# OC_PROT.net
KiCad netlist of a schematic drawn in Altium Designer
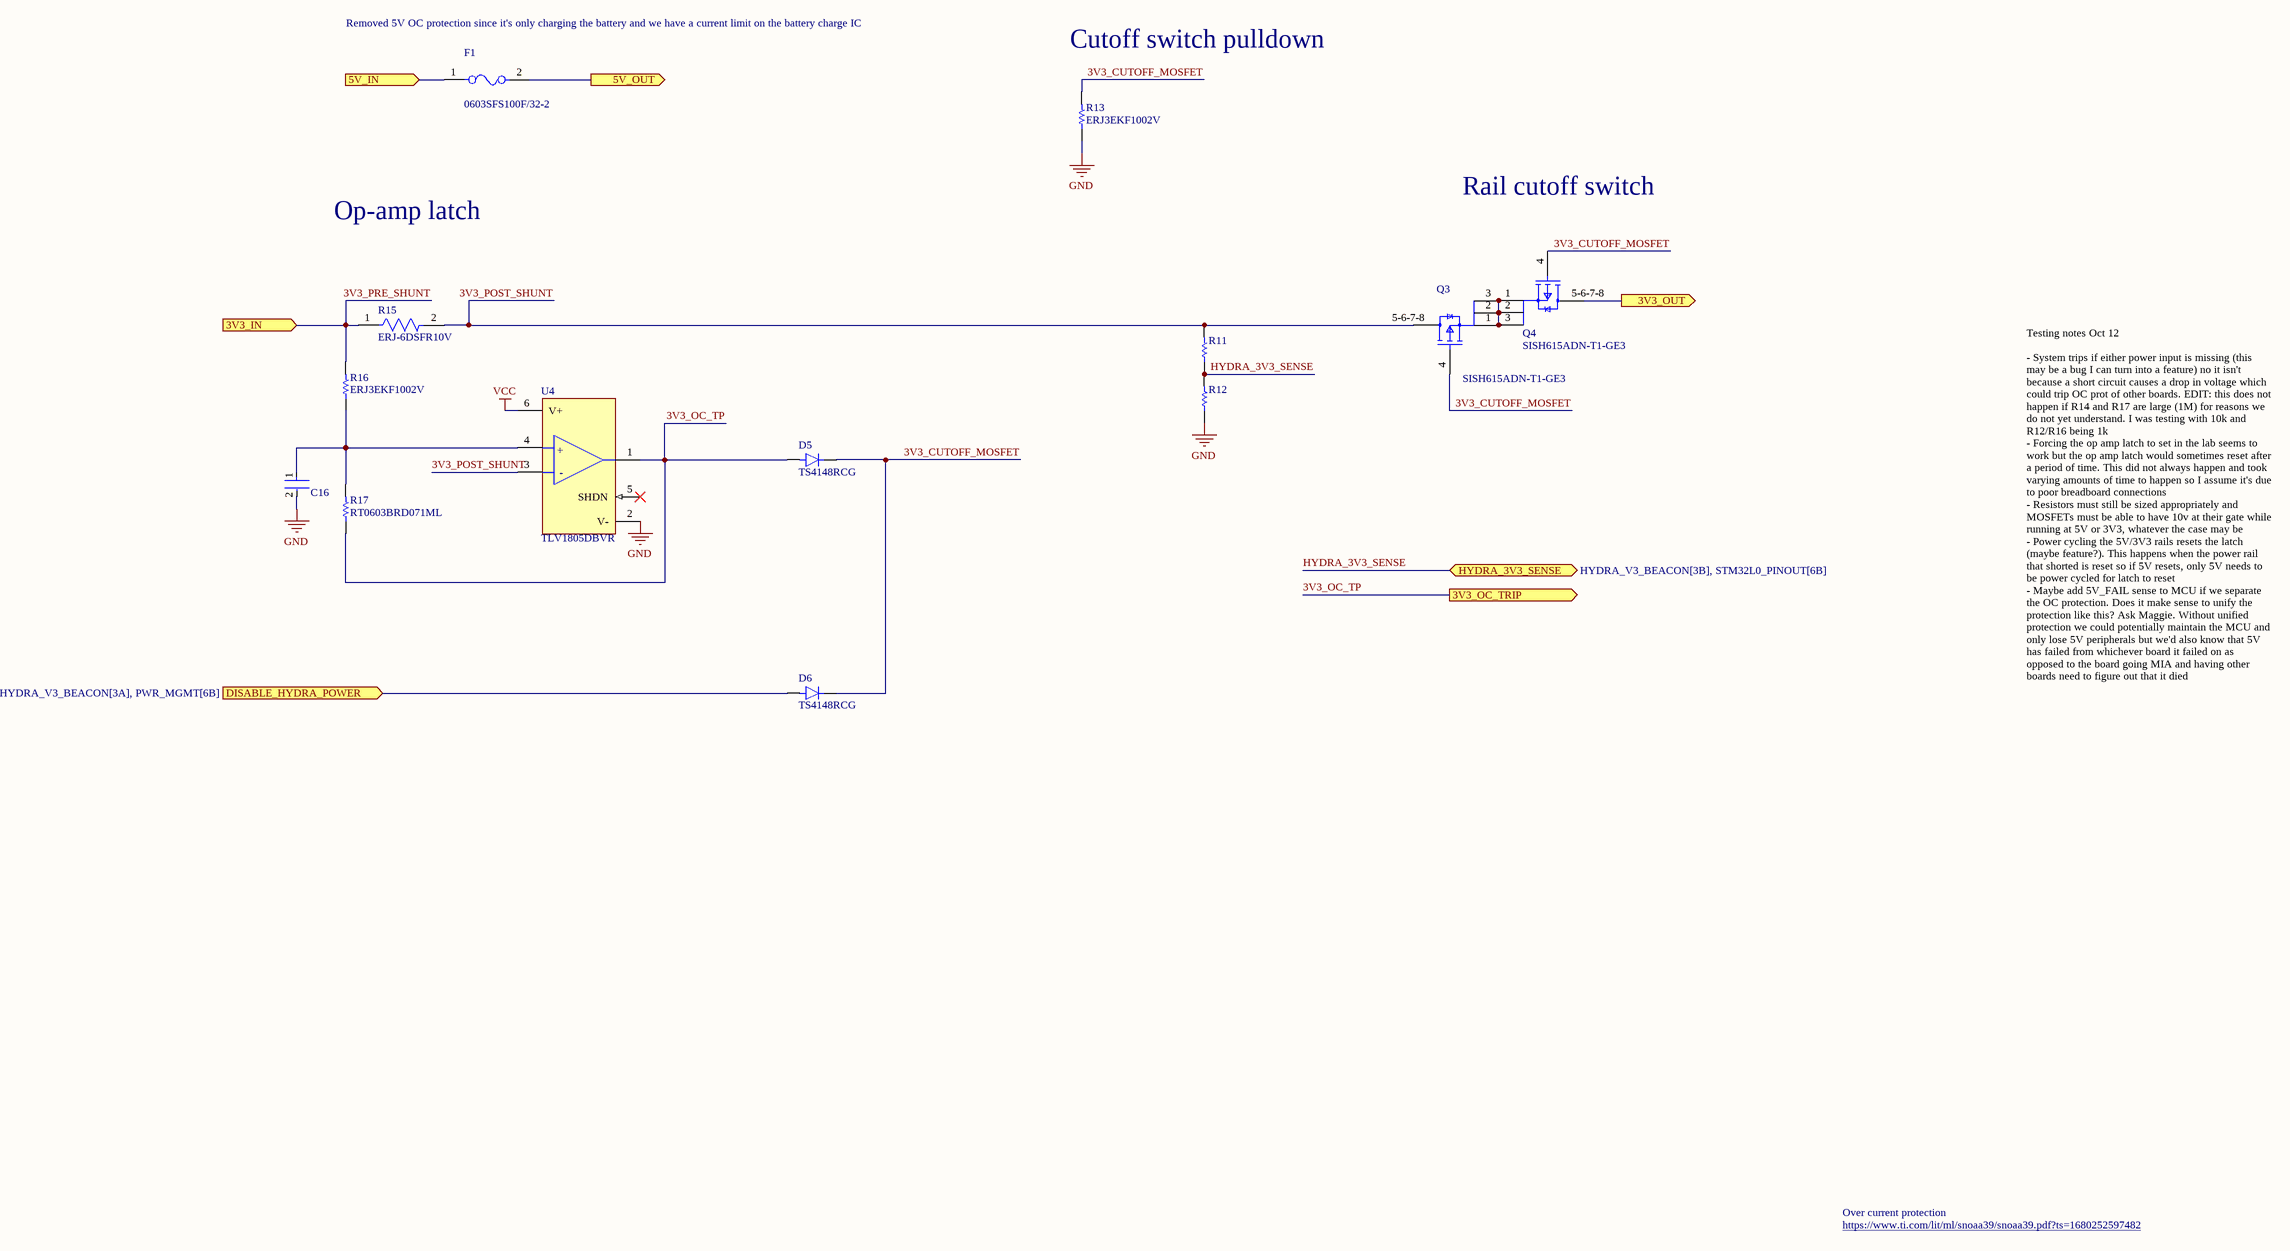
[diagram p0: OC_PROT.SchDoc]

(export (version "E")
  (design (tool "Eeschema 10.0.6"))
  (components
    (comp (ref "C16")
      (value "C0402C104K8PACTU")
      (footprint "FP-C0402-BB-MFG")
      (description "CAP CER 0.1UF 10V X5R 0402")
      (fields (field (name "MANUFACTURER") "Kemet") (field (name "TOLERANCE") "0.1"))
      (libsource (lib "Altium Content Vault") (part "b4654b650e69147ec39a6b967a45e02"))
    )
    (comp (ref "D5")
      (value "TS4148RCG")
      (footprint "TS4148RCG-Footprint-1")
      (description "SMD Si-Diode 75V 100mA 0603")
      (libsource (lib "uORocketry Hardware") (part "TS4148RCG"))
    )
    (comp (ref "D6")
      (value "TS4148RCG")
      (footprint "TS4148RCG-Footprint-1")
      (description "SMD Si-Diode 75V 100mA 0603")
      (libsource (lib "uORocketry Hardware") (part "TS4148RCG"))
    )
    (comp (ref "F1")
      (value "0603SFS100F/32-2")
      (footprint "FP-0603SFS-MFG")
      (description "FUSE BOARD MOUNT 1A 32VDC 0603")
      (fields
        (field (name "OCTOPART") "https://octopart.com/0603sfs100f%2F32-2-littelfuse-74214378")
        (field (name "MANUFACTURER") "Littelfuse")
      )
      (libsource (lib "Altium Content Vault") (part "5bcf9b9f640e542cf0359d10258e979"))
    )
    (comp (ref "Q3")
      (value "SISH615ADN-T1-GE3")
      (footprint "SISH615ADN-T1-GE3-Footprint-1")
      (description "Trans MOSFET P-CH 20V 22.1A 8-Pin PowerPAK 1212 EP T/R")
      (libsource (lib "uORocketry Hardware") (part "SISH615ADN-T1-GE3-Symbol-1"))
    )
    (comp (ref "Q4")
      (value "SISH615ADN-T1-GE3")
      (footprint "SISH615ADN-T1-GE3-Footprint-1")
      (description "Trans MOSFET P-CH 20V 22.1A 8-Pin PowerPAK 1212 EP T/R")
      (libsource (lib "uORocketry Hardware") (part "SISH615ADN-T1-GE3-Symbol-1"))
    )
    (comp (ref "R11")
      (value "ERJ3EKF1002V")
      (footprint "RESC1609X55X30LL15T15")
      (description "Chip Resistor, 10 KOhm, +/- 1%, 0.1 W, -55 to 155 degC, 0603 (1608 Metric), RoHS, Tape and Reel")
      (fields (field (name "TOLERANCE") "1%") (field (name "MANUFACTURER") "Panasonic"))
      (libsource (lib "Altium Content Vault") (part "RES-2"))
    )
    (comp (ref "R12")
      (value "ERJ3EKF1002V")
      (footprint "RESC1609X55X30LL15T15")
      (description "Chip Resistor, 10 KOhm, +/- 1%, 0.1 W, -55 to 155 degC, 0603 (1608 Metric), RoHS, Tape and Reel")
      (fields (field (name "TOLERANCE") "1%") (field (name "MANUFACTURER") "Panasonic"))
      (libsource (lib "Altium Content Vault") (part "RES-2"))
    )
    (comp (ref "R13")
      (value "ERJ3EKF1002V")
      (footprint "RESC1609X55X30LL15T15")
      (description "Chip Resistor, 10 KOhm, +/- 1%, 0.1 W, -55 to 155 degC, 0603 (1608 Metric), RoHS, Tape and Reel")
      (fields (field (name "TOLERANCE") "1%") (field (name "MANUFACTURER") "Panasonic"))
      (libsource (lib "Altium Content Vault") (part "RES-2"))
    )
    (comp (ref "R15")
      (value "ERJ-6DSFR10V")
      (footprint "FP-ERJ6D-MFG")
      (description "RES 0.1 OHM 1% 1/2W 0805")
      (fields (field (name "TOLERANCE") "1%"))
      (libsource (lib "Altium Content Vault") (part "1029c3af85768c4190bb7ad29bc67b5"))
    )
    (comp (ref "R16")
      (value "ERJ3EKF1002V")
      (footprint "RESC1609X55X30LL15T15")
      (description "Chip Resistor, 10 KOhm, +/- 1%, 0.1 W, -55 to 155 degC, 0603 (1608 Metric), RoHS, Tape and Reel")
      (fields (field (name "TOLERANCE") "1%") (field (name "MANUFACTURER") "Panasonic"))
      (libsource (lib "Altium Content Vault") (part "RES-2"))
    )
    (comp (ref "R17")
      (value "RT0603BRD071ML")
      (footprint "RESC1608X55X30NL20T20")
      (fields (field (name "MANUFACTURER") "Panasonic") (field (name "PART NUMBER") "ERA-3AEB163V"))
      (libsource (lib "Altium Content Vault") (part "RES"))
    )
    (comp (ref "U4")
      (value "TLV1805DBVR")
      (footprint "FP-DBV0006A-IPC_C")
      (description "40V, RAIL-TO-RAIL INPUT, PUSH-PU")
      (libsource (lib "Altium Content Vault") (part "c7aa3bc3dbf0dc8b0b0354779bd1228"))
    )
  )
  (nets
    (net (code "1") (name "/3V3_CUTOFF_MOSFET") (class "Default")
      (node (ref "D5") (pin "C") (pinfunction "K_C") (pintype "passive"))
      (node (ref "D6") (pin "C") (pinfunction "K_C") (pintype "passive"))
      (node (ref "Q3") (pin "4") (pinfunction "G_4") (pintype "passive"))
      (node (ref "Q4") (pin "4") (pinfunction "G_4") (pintype "passive"))
      (node (ref "R13") (pin "2") (pinfunction "2_2") (pintype "passive"))
    )
    (net (code "2") (name "/3V3_OC_TP") (class "Default")
      (node (ref "D5") (pin "A") (pinfunction "A_A") (pintype "passive"))
      (node (ref "R17") (pin "1") (pinfunction "1_1") (pintype "passive"))
      (node (ref "U4") (pin "1") (pinfunction "OUT_1") (pintype "passive"))
    )
    (net (code "3") (name "/3V3_OUT") (class "Default")
      (node (ref "Q4") (pin "5-6-7-8") (pinfunction "D_5-6-7-8") (pintype "passive"))
    )
    (net (code "4") (name "/3V3_POST_SHUNT") (class "Default")
      (node (ref "Q3") (pin "5-6-7-8") (pinfunction "D_5-6-7-8") (pintype "passive"))
      (node (ref "R11") (pin "2") (pinfunction "2_2") (pintype "passive"))
      (node (ref "R15") (pin "2") (pinfunction "2_2") (pintype "passive"))
      (node (ref "U4") (pin "3") (pinfunction "-IN_3") (pintype "tri_state"))
    )
    (net (code "5") (name "/3V3_PRE_SHUNT") (class "Default")
      (node (ref "R15") (pin "1") (pinfunction "1_1") (pintype "passive"))
      (node (ref "R16") (pin "2") (pinfunction "2_2") (pintype "passive"))
    )
    (net (code "6") (name "/5V_IN") (class "Default")
      (node (ref "F1") (pin "1") (pinfunction "1_1") (pintype "passive"))
    )
    (net (code "7") (name "/5V_OUT") (class "Default")
      (node (ref "F1") (pin "2") (pinfunction "2_2") (pintype "passive"))
    )
    (net (code "8") (name "/DISABLE_HYDRA_POWER") (class "Default")
      (node (ref "D6") (pin "A") (pinfunction "A_A") (pintype "passive"))
    )
    (net (code "9") (name "/HYDRA_3V3_SENSE") (class "Default")
      (node (ref "R11") (pin "1") (pinfunction "1_1") (pintype "passive"))
      (node (ref "R12") (pin "2") (pinfunction "2_2") (pintype "passive"))
    )
    (net (code "10") (name "GND") (class "Default")
      (node (ref "C16") (pin "2") (pinfunction "2_2") (pintype "passive"))
      (node (ref "R12") (pin "1") (pinfunction "1_1") (pintype "passive"))
      (node (ref "R13") (pin "1") (pinfunction "1_1") (pintype "passive"))
      (node (ref "U4") (pin "2") (pinfunction "V-_2") (pintype "power_in"))
    )
    (net (code "11") (name "Net-(Q3-S-Pad1)") (class "Default")
      (node (ref "Q3") (pin "1") (pinfunction "S_1") (pintype "passive"))
      (node (ref "Q3") (pin "2") (pinfunction "S_2") (pintype "passive"))
      (node (ref "Q3") (pin "3") (pinfunction "S_3") (pintype "passive"))
      (node (ref "Q4") (pin "1") (pinfunction "S_1") (pintype "passive"))
      (node (ref "Q4") (pin "2") (pinfunction "S_2") (pintype "passive"))
      (node (ref "Q4") (pin "3") (pinfunction "S_3") (pintype "passive"))
    )
    (net (code "12") (name "Net-(U4-+IN)") (class "Default")
      (node (ref "C16") (pin "1") (pinfunction "1_1") (pintype "passive"))
      (node (ref "R16") (pin "1") (pinfunction "1_1") (pintype "passive"))
      (node (ref "R17") (pin "2") (pinfunction "2_2") (pintype "passive"))
      (node (ref "U4") (pin "4") (pinfunction "+IN_4") (pintype "tri_state"))
    )
    (net (code "13") (name "VCC") (class "Default")
      (node (ref "U4") (pin "6") (pinfunction "V+_6") (pintype "power_in"))
    )
    (net (code "14") (name "unconnected-(U4-SHDN-Pad5)") (class "Default")
      (node (ref "U4") (pin "5") (pinfunction "SHDN_5") (pintype "input+no_connect"))
    )
  )
)
